# pihat.net
KiCad netlist of a schematic drawn in EAGLE
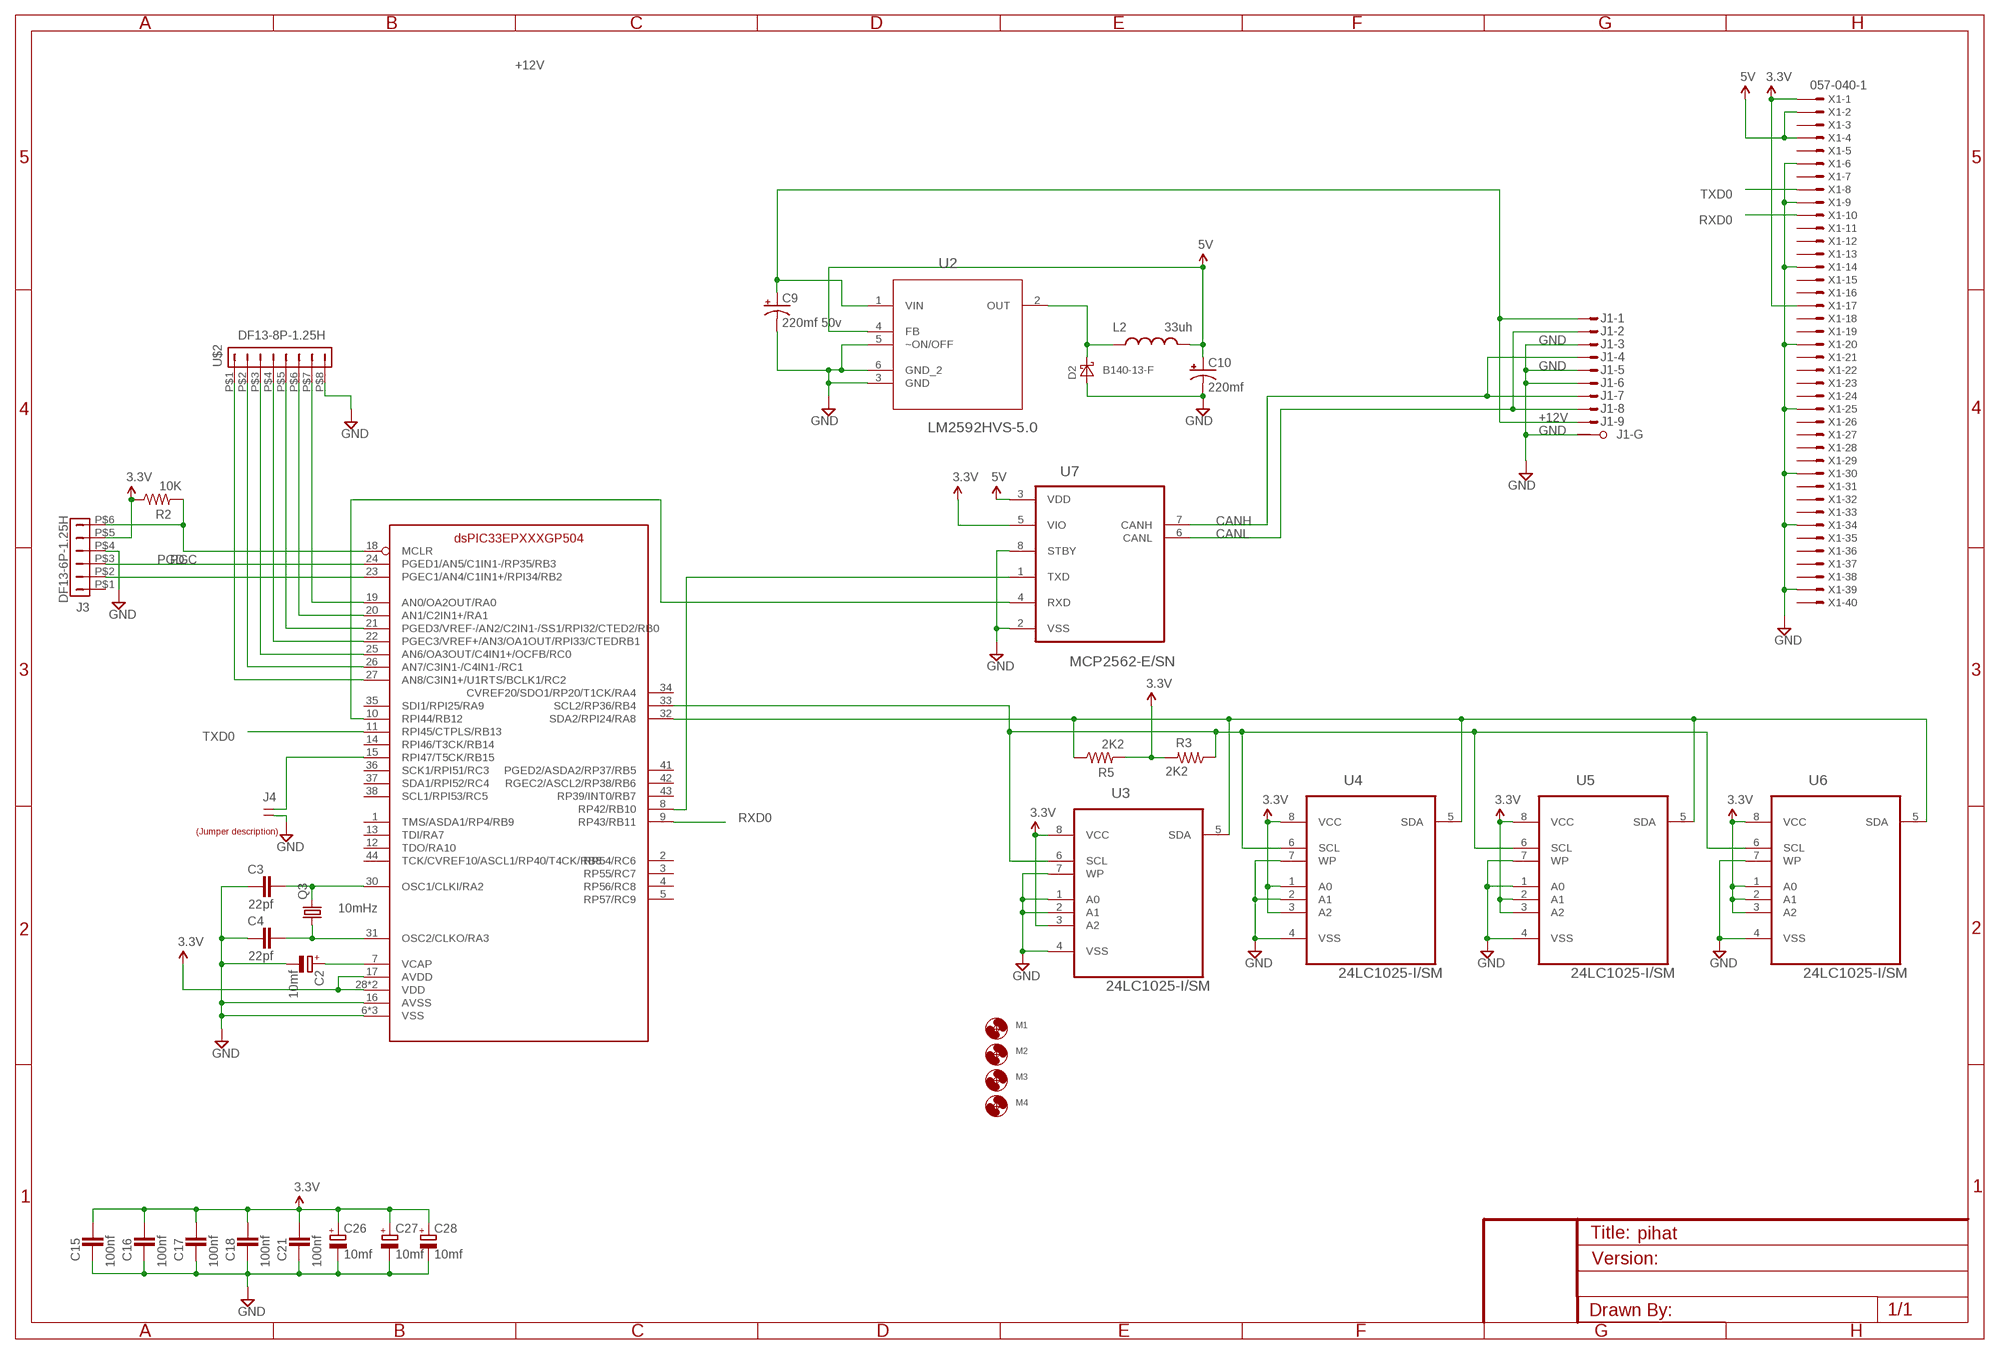
[diagram p0: schematic, sheet 1]

(export (version "E")
  (design (tool "Eeschema 10.0.6"))
  (components
    (comp (ref "C2")
      (value "10mf")
      (footprint "eagle-import:SMC_A")
      (fields (field (name "PARTNO") "T491A106K004AT"))
      (libsource (lib "eagle-import") (part "CAPACITOR_POL-SMC_A"))
    )
    (comp (ref "C3")
      (value "22pf")
      (footprint "eagle-import:C805")
      (fields (field (name "PARTNO") "C0805C220J5GACTU"))
      (libsource (lib "eagle-import") (part "CAPACITOR_NPOL-0805"))
    )
    (comp (ref "C4")
      (value "22pf")
      (footprint "eagle-import:C805")
      (fields (field (name "PARTNO") "C0805C220J5GACTU"))
      (libsource (lib "eagle-import") (part "CAPACITOR_NPOL-0805"))
    )
    (comp (ref "C9")
      (value "220mf 50v")
      (footprint "eagle-import:EIA7343")
      (fields (field (name "PARTNO") "T545X227M016ATE035"))
      (libsource (lib "eagle-import") (part "CAP_POL7343"))
    )
    (comp (ref "C10")
      (value "220mf")
      (footprint "eagle-import:EIA7343")
      (fields (field (name "PARTNO") "T545X227M016ATE035"))
      (libsource (lib "eagle-import") (part "CAP_POL7343"))
    )
    (comp (ref "C15")
      (value "100nf")
      (footprint "eagle-import:C805")
      (fields (field (name "PARTNO") "CL21F104ZBCNNNC"))
      (libsource (lib "eagle-import") (part "CAPACITOR_NPOL-0805"))
    )
    (comp (ref "C16")
      (value "100nf")
      (footprint "eagle-import:C805")
      (fields (field (name "PARTNO") "CL21F104ZBCNNNC"))
      (libsource (lib "eagle-import") (part "CAPACITOR_NPOL-0805"))
    )
    (comp (ref "C17")
      (value "100nf")
      (footprint "eagle-import:C805")
      (fields (field (name "PARTNO") "CL21F104ZBCNNNC"))
      (libsource (lib "eagle-import") (part "CAPACITOR_NPOL-0805"))
    )
    (comp (ref "C18")
      (value "100nf")
      (footprint "eagle-import:C805")
      (fields (field (name "PARTNO") "CL21F104ZBCNNNC"))
      (libsource (lib "eagle-import") (part "CAPACITOR_NPOL-0805"))
    )
    (comp (ref "C21")
      (value "100nf")
      (footprint "eagle-import:C805")
      (fields (field (name "PARTNO") "CL21F104ZBCNNNC"))
      (libsource (lib "eagle-import") (part "CAPACITOR_NPOL-0805"))
    )
    (comp (ref "C26")
      (value "10mf")
      (footprint "eagle-import:SMC_A")
      (fields (field (name "PARTNO") "T491A106K004AT"))
      (libsource (lib "eagle-import") (part "CAPACITOR_POL-SMC_A"))
    )
    (comp (ref "C27")
      (value "10mf")
      (footprint "eagle-import:SMC_A")
      (fields (field (name "PARTNO") "T491A106K004AT"))
      (libsource (lib "eagle-import") (part "CAPACITOR_POL-SMC_A"))
    )
    (comp (ref "C28")
      (value "10mf")
      (footprint "eagle-import:SMC_A")
      (fields (field (name "PARTNO") "T491A106K004AT"))
      (libsource (lib "eagle-import") (part "CAPACITOR_POL-SMC_A"))
    )
    (comp (ref "D2")
      (value "B140-13-F")
      (footprint "eagle-import:SMA")
      (libsource (lib "eagle-import") (part "DIODE-SCHOTTKY-SMA"))
    )
    (comp (ref "J1")
      (value "M09VPS")
      (footprint "eagle-import:M09VP")
      (fields (field (name "PARTNO") "1-1634218-2"))
      (libsource (lib "eagle-import") (part "M09VPS"))
    )
    (comp (ref "J3")
      (value "DF13-6P-1.25H")
      (footprint "eagle-import:DF13A-6P-1.25H")
      (fields (field (name "PARTNO") "DF13A-6P-1.25H(20)"))
      (libsource (lib "eagle-import") (part "DF13-6P-1.25H"))
    )
    (comp (ref "J4")
      (value "JUMPER-1X2")
      (footprint "eagle-import:JUMPER-1X2")
      (fields (field (name "PARTNO") "M20-9770246"))
      (libsource (lib "eagle-import") (part "JUMPER-1X2"))
    )
    (comp (ref "L2")
      (value "33uh")
      (footprint "eagle-import:1812")
      (fields (field (name "PARTNO") "B78108S1333K"))
      (libsource (lib "eagle-import") (part "INDUCTOR"))
    )
    (comp (ref "M1")
      (value "MOUNT-HOLE2.8")
      (footprint "eagle-import:2,8")
      (libsource (lib "eagle-import") (part "MOUNT-HOLE2.8"))
    )
    (comp (ref "M2")
      (value "MOUNT-HOLE2.8")
      (footprint "eagle-import:2,8")
      (libsource (lib "eagle-import") (part "MOUNT-HOLE2.8"))
    )
    (comp (ref "M3")
      (value "MOUNT-HOLE2.8")
      (footprint "eagle-import:2,8")
      (libsource (lib "eagle-import") (part "MOUNT-HOLE2.8"))
    )
    (comp (ref "M4")
      (value "MOUNT-HOLE2.8")
      (footprint "eagle-import:2,8")
      (libsource (lib "eagle-import") (part "MOUNT-HOLE2.8"))
    )
    (comp (ref "Q3")
      (value "10mHz")
      (footprint "eagle-import:HC49_S")
      (fields (field (name "PARTNO") "ATS100B-E"))
      (libsource (lib "eagle-import") (part "CRYSTALHC49S"))
    )
    (comp (ref "R2")
      (value "10K")
      (footprint "eagle-import:0603-RES")
      (fields (field (name "PARTNO") "RC0603FR-0710KL"))
      (libsource (lib "eagle-import") (part "RESISTOR0603-RES"))
    )
    (comp (ref "R3")
      (value "2K2")
      (footprint "eagle-import:0603-RES")
      (fields (field (name "PARTNO") "RC0603FR-072K2L"))
      (libsource (lib "eagle-import") (part "RESISTOR0603-RES"))
    )
    (comp (ref "R5")
      (value "2K2")
      (footprint "eagle-import:0603-RES")
      (fields (field (name "PARTNO") "RC0603FR-072K2L"))
      (libsource (lib "eagle-import") (part "RESISTOR0603-RES"))
    )
    (comp (ref "U$1")
      (value "LABEL_JUMPER_1X2")
      (footprint "eagle-import:JUMP2_DESC")
      (fields (field (name "OFF") "Normal") (field (name "ON") "Reset"))
      (libsource (lib "eagle-import") (part "LABEL_JUMPER_1X2"))
    )
    (comp (ref "U$2")
      (value "DF13-8P-1.25H")
      (footprint "eagle-import:DF13A-8P-1.25H")
      (fields (field (name "PARTNO") "DF13-8P-1.25H(50)"))
      (libsource (lib "eagle-import") (part "DF13-8P-1.25H"))
    )
    (comp (ref "U1")
      (value "DSPIC33EPXXXGP504")
      (footprint "eagle-import:TQFP44")
      (fields (field (name "PARTNO") "DSPIC33EP512GP504-I/PT"))
      (libsource (lib "eagle-import") (part "DSPIC33EPXXXGP504"))
    )
    (comp (ref "U2")
      (value "LM2592HVS-5.0")
      (footprint "eagle-import:TO170P1435X457-5N")
      (fields (field (name "PARTNO") "LM2592HVSX-5.0/NOPB"))
      (libsource (lib "eagle-import") (part "LM2592HVS-5.0"))
    )
    (comp (ref "U3")
      (value "24LC1025-I/SM")
      (footprint "eagle-import:SOIC8-N_MC")
      (fields (field (name "PARTNO") "24LC1025T-I/SN"))
      (libsource (lib "eagle-import") (part "24LC1025-I/SM"))
    )
    (comp (ref "U4")
      (value "24LC1025-I/SM")
      (footprint "eagle-import:SOIC8-N_MC")
      (fields (field (name "PARTNO") "24LC1025T-I/SN"))
      (libsource (lib "eagle-import") (part "24LC1025-I/SM"))
    )
    (comp (ref "U5")
      (value "24LC1025-I/SM")
      (footprint "eagle-import:SOIC8-N_MC")
      (fields (field (name "PARTNO") "24LC1025T-I/SN"))
      (libsource (lib "eagle-import") (part "24LC1025-I/SM"))
    )
    (comp (ref "U6")
      (value "24LC1025-I/SM")
      (footprint "eagle-import:SOIC8-N_MC")
      (fields (field (name "PARTNO") "24LC1025T-I/SN"))
      (libsource (lib "eagle-import") (part "24LC1025-I/SM"))
    )
    (comp (ref "U7")
      (value "MCP2562-E/SN")
      (footprint "eagle-import:SOIC-8N")
      (libsource (lib "eagle-import") (part "MCP2562-E/SN"))
    )
    (comp (ref "X1")
      (value "057-040-1")
      (footprint "eagle-import:057-040-1")
      (libsource (lib "eagle-import") (part "057-040-1"))
    )
  )
  (nets
    (net (code "1") (name "/+12V") (class "Default")
      (node (ref "C9") (pin "A") (pinfunction "+_A") (pintype "passive"))
      (node (ref "J1") (pin "1") (pinfunction "M_1") (pintype "passive"))
      (node (ref "J1") (pin "9") (pinfunction "M_9") (pintype "passive"))
      (node (ref "U2") (pin "1") (pinfunction "VIN_1") (pintype "power_in"))
    )
    (net (code "2") (name "/CANH") (class "Default")
      (node (ref "J1") (pin "4") (pinfunction "M_4") (pintype "passive"))
      (node (ref "J1") (pin "7") (pinfunction "M_7") (pintype "passive"))
      (node (ref "U7") (pin "7") (pinfunction "CANH_7") (pintype "bidirectional"))
    )
    (net (code "3") (name "/CANL") (class "Default")
      (node (ref "J1") (pin "2") (pinfunction "M_2") (pintype "passive"))
      (node (ref "J1") (pin "8") (pinfunction "M_8") (pintype "passive"))
      (node (ref "U7") (pin "6") (pinfunction "CANL_6") (pintype "bidirectional"))
    )
    (net (code "4") (name "/PGC") (class "Default")
      (node (ref "J3") (pin "P$2") (pinfunction "2_P$2") (pintype "passive"))
      (node (ref "U1") (pin "23") (pinfunction "PGEC1/AN4/C1IN1+/RPI34/RB2_23") (pintype "bidirectional"))
    )
    (net (code "5") (name "/PGD") (class "Default")
      (node (ref "J3") (pin "P$3") (pinfunction "3_P$3") (pintype "passive"))
      (node (ref "U1") (pin "24") (pinfunction "PGED1/AN5/C1IN1-/RP35/RB3_24") (pintype "bidirectional"))
    )
    (net (code "6") (name "/RXD0") (class "Default")
      (node (ref "U1") (pin "9") (pinfunction "RP43/RB11_9") (pintype "bidirectional"))
      (node (ref "X1") (pin "10") (pinfunction "S_10") (pintype "passive"))
    )
    (net (code "7") (name "/TXD0") (class "Default")
      (node (ref "U1") (pin "11") (pinfunction "RPI45/CTPLS/RB13_11") (pintype "bidirectional"))
      (node (ref "X1") (pin "8") (pinfunction "S_8") (pintype "passive"))
    )
    (net (code "8") (name "3.3V") (class "Default")
      (node (ref "C15") (pin "1") (pinfunction "1_1") (pintype "passive"))
      (node (ref "C16") (pin "1") (pinfunction "1_1") (pintype "passive"))
      (node (ref "C17") (pin "1") (pinfunction "1_1") (pintype "passive"))
      (node (ref "C18") (pin "1") (pinfunction "1_1") (pintype "passive"))
      (node (ref "C21") (pin "1") (pinfunction "1_1") (pintype "passive"))
      (node (ref "C26") (pin "+") (pinfunction "+_+") (pintype "passive"))
      (node (ref "C27") (pin "+") (pinfunction "+_+") (pintype "passive"))
      (node (ref "C28") (pin "+") (pinfunction "+_+") (pintype "passive"))
      (node (ref "J3") (pin "P$5") (pinfunction "5_P$5") (pintype "passive"))
      (node (ref "R2") (pin "1") (pinfunction "1_1") (pintype "passive"))
      (node (ref "R3") (pin "2") (pinfunction "2_2") (pintype "passive"))
      (node (ref "R5") (pin "2") (pinfunction "2_2") (pintype "passive"))
      (node (ref "U1") (pin "17") (pinfunction "AVDD_17") (pintype "bidirectional"))
      (node (ref "U1") (pin "28") (pinfunction "VDD_28") (pintype "bidirectional"))
      (node (ref "U1") (pin "40") (pinfunction "VDD_40") (pintype "bidirectional"))
      (node (ref "U3") (pin "3") (pinfunction "A2_3") (pintype "input"))
      (node (ref "U3") (pin "8") (pinfunction "VCC_8") (pintype "power_in"))
      (node (ref "U4") (pin "1") (pinfunction "A0_1") (pintype "input"))
      (node (ref "U4") (pin "3") (pinfunction "A2_3") (pintype "input"))
      (node (ref "U4") (pin "8") (pinfunction "VCC_8") (pintype "power_in"))
      (node (ref "U5") (pin "2") (pinfunction "A1_2") (pintype "input"))
      (node (ref "U5") (pin "3") (pinfunction "A2_3") (pintype "input"))
      (node (ref "U5") (pin "8") (pinfunction "VCC_8") (pintype "power_in"))
      (node (ref "U6") (pin "1") (pinfunction "A0_1") (pintype "input"))
      (node (ref "U6") (pin "2") (pinfunction "A1_2") (pintype "input"))
      (node (ref "U6") (pin "3") (pinfunction "A2_3") (pintype "input"))
      (node (ref "U6") (pin "8") (pinfunction "VCC_8") (pintype "power_in"))
      (node (ref "U7") (pin "5") (pinfunction "VIO_5") (pintype "power_in"))
      (node (ref "X1") (pin "1") (pinfunction "S_1") (pintype "passive"))
      (node (ref "X1") (pin "17") (pinfunction "S_17") (pintype "passive"))
    )
    (net (code "9") (name "5V") (class "Default")
      (node (ref "C10") (pin "A") (pinfunction "+_A") (pintype "passive"))
      (node (ref "L2") (pin "2") (pinfunction "2_2") (pintype "passive"))
      (node (ref "U2") (pin "4") (pinfunction "FB_4") (pintype "input"))
      (node (ref "U7") (pin "3") (pinfunction "VDD_3") (pintype "power_in"))
      (node (ref "X1") (pin "2") (pinfunction "S_2") (pintype "passive"))
      (node (ref "X1") (pin "4") (pinfunction "S_4") (pintype "passive"))
    )
    (net (code "10") (name "GND") (class "Default")
      (node (ref "C10") (pin "C") (pinfunction "-_C") (pintype "passive"))
      (node (ref "C15") (pin "2") (pinfunction "2_2") (pintype "passive"))
      (node (ref "C16") (pin "2") (pinfunction "2_2") (pintype "passive"))
      (node (ref "C17") (pin "2") (pinfunction "2_2") (pintype "passive"))
      (node (ref "C18") (pin "2") (pinfunction "2_2") (pintype "passive"))
      (node (ref "C2") (pin "-") (pinfunction "-_-") (pintype "passive"))
      (node (ref "C21") (pin "2") (pinfunction "2_2") (pintype "passive"))
      (node (ref "C26") (pin "-") (pinfunction "-_-") (pintype "passive"))
      (node (ref "C27") (pin "-") (pinfunction "-_-") (pintype "passive"))
      (node (ref "C28") (pin "-") (pinfunction "-_-") (pintype "passive"))
      (node (ref "C3") (pin "2") (pinfunction "2_2") (pintype "passive"))
      (node (ref "C4") (pin "2") (pinfunction "2_2") (pintype "passive"))
      (node (ref "C9") (pin "C") (pinfunction "-_C") (pintype "passive"))
      (node (ref "D2") (pin "A") (pinfunction "A_A") (pintype "passive"))
      (node (ref "J1") (pin "3") (pinfunction "M_3") (pintype "passive"))
      (node (ref "J1") (pin "5") (pinfunction "M_5") (pintype "passive"))
      (node (ref "J1") (pin "6") (pinfunction "M_6") (pintype "passive"))
      (node (ref "J1") (pin "G1") (pinfunction "G1_G1") (pintype "passive"))
      (node (ref "J3") (pin "P$4") (pinfunction "4_P$4") (pintype "passive"))
      (node (ref "J4") (pin "2") (pinfunction "2_2") (pintype "bidirectional"))
      (node (ref "U$2") (pin "P$8") (pinfunction "8_P$8") (pintype "passive"))
      (node (ref "U1") (pin "16") (pinfunction "AVSS_16") (pintype "bidirectional"))
      (node (ref "U1") (pin "29") (pinfunction "VSS_29") (pintype "bidirectional"))
      (node (ref "U1") (pin "39") (pinfunction "VSS_39") (pintype "bidirectional"))
      (node (ref "U1") (pin "6") (pinfunction "VSS_6") (pintype "bidirectional"))
      (node (ref "U2") (pin "3") (pinfunction "GND_3") (pintype "passive"))
      (node (ref "U2") (pin "5") (pinfunction "~{ON/OFF}_5") (pintype "input"))
      (node (ref "U2") (pin "6") (pinfunction "GND_2_6") (pintype "passive"))
      (node (ref "U3") (pin "1") (pinfunction "A0_1") (pintype "input"))
      (node (ref "U3") (pin "2") (pinfunction "A1_2") (pintype "input"))
      (node (ref "U3") (pin "4") (pinfunction "VSS_4") (pintype "passive"))
      (node (ref "U3") (pin "7") (pinfunction "WP_7") (pintype "input"))
      (node (ref "U4") (pin "2") (pinfunction "A1_2") (pintype "input"))
      (node (ref "U4") (pin "4") (pinfunction "VSS_4") (pintype "passive"))
      (node (ref "U4") (pin "7") (pinfunction "WP_7") (pintype "input"))
      (node (ref "U5") (pin "1") (pinfunction "A0_1") (pintype "input"))
      (node (ref "U5") (pin "4") (pinfunction "VSS_4") (pintype "passive"))
      (node (ref "U5") (pin "7") (pinfunction "WP_7") (pintype "input"))
      (node (ref "U6") (pin "4") (pinfunction "VSS_4") (pintype "passive"))
      (node (ref "U6") (pin "7") (pinfunction "WP_7") (pintype "input"))
      (node (ref "U7") (pin "2") (pinfunction "VSS_2") (pintype "power_in"))
      (node (ref "U7") (pin "8") (pinfunction "STBY_8") (pintype "input"))
      (node (ref "X1") (pin "14") (pinfunction "S_14") (pintype "passive"))
      (node (ref "X1") (pin "20") (pinfunction "S_20") (pintype "passive"))
      (node (ref "X1") (pin "25") (pinfunction "S_25") (pintype "passive"))
      (node (ref "X1") (pin "30") (pinfunction "S_30") (pintype "passive"))
      (node (ref "X1") (pin "34") (pinfunction "S_34") (pintype "passive"))
      (node (ref "X1") (pin "39") (pinfunction "S_39") (pintype "passive"))
      (node (ref "X1") (pin "6") (pinfunction "S_6") (pintype "passive"))
      (node (ref "X1") (pin "9") (pinfunction "S_9") (pintype "passive"))
    )
    (net (code "11") (name "Net-(J3-6)") (class "Default")
      (node (ref "J3") (pin "P$6") (pinfunction "6_P$6") (pintype "passive"))
      (node (ref "R2") (pin "2") (pinfunction "2_2") (pintype "passive"))
      (node (ref "U1") (pin "18") (pinfunction "MCLR_18") (pintype "input"))
    )
    (net (code "12") (name "Net-(U$2-1)") (class "Default")
      (node (ref "U$2") (pin "P$1") (pinfunction "1_P$1") (pintype "passive"))
      (node (ref "U1") (pin "27") (pinfunction "AN8/C3IN1+/U1RTS/BCLK1/RC2_27") (pintype "bidirectional"))
    )
    (net (code "13") (name "Net-(U$2-2)") (class "Default")
      (node (ref "U$2") (pin "P$2") (pinfunction "2_P$2") (pintype "passive"))
      (node (ref "U1") (pin "26") (pinfunction "AN7/C3IN1-/C4IN1-/RC1_26") (pintype "bidirectional"))
    )
    (net (code "14") (name "Net-(U$2-3)") (class "Default")
      (node (ref "U$2") (pin "P$3") (pinfunction "3_P$3") (pintype "passive"))
      (node (ref "U1") (pin "25") (pinfunction "AN6/OA3OUT/C4IN1+/OCFB/RC0_25") (pintype "bidirectional"))
    )
    (net (code "15") (name "Net-(U$2-4)") (class "Default")
      (node (ref "U$2") (pin "P$4") (pinfunction "4_P$4") (pintype "passive"))
      (node (ref "U1") (pin "22") (pinfunction "PGEC3/VREF+/AN3/OA1OUT/RPI33/CTEDRB1_22") (pintype "bidirectional"))
    )
    (net (code "16") (name "Net-(U$2-5)") (class "Default")
      (node (ref "U$2") (pin "P$5") (pinfunction "5_P$5") (pintype "passive"))
      (node (ref "U1") (pin "21") (pinfunction "PGED3/VREF-/AN2/C2IN1-/SS1/RPI32/CTED2/RB0_21") (pintype "bidirectional"))
    )
    (net (code "17") (name "Net-(U$2-6)") (class "Default")
      (node (ref "U$2") (pin "P$6") (pinfunction "6_P$6") (pintype "passive"))
      (node (ref "U1") (pin "20") (pinfunction "AN1/C2IN1+/RA1_20") (pintype "bidirectional"))
    )
    (net (code "18") (name "Net-(U$2-7)") (class "Default")
      (node (ref "U$2") (pin "P$7") (pinfunction "7_P$7") (pintype "passive"))
      (node (ref "U1") (pin "19") (pinfunction "AN0/OA2OUT/RA0_19") (pintype "bidirectional"))
    )
    (net (code "19") (name "Net-(U1-OSC1{slash}CLKI{slash}RA2)") (class "Default")
      (node (ref "C3") (pin "1") (pinfunction "1_1") (pintype "passive"))
      (node (ref "Q3") (pin "2") (pinfunction "2_2") (pintype "passive"))
      (node (ref "U1") (pin "30") (pinfunction "OSC1/CLKI/RA2_30") (pintype "bidirectional"))
    )
    (net (code "20") (name "Net-(U1-OSC2{slash}CLKO{slash}RA3)") (class "Default")
      (node (ref "C4") (pin "1") (pinfunction "1_1") (pintype "passive"))
      (node (ref "Q3") (pin "1") (pinfunction "1_1") (pintype "passive"))
      (node (ref "U1") (pin "31") (pinfunction "OSC2/CLKO/RA3_31") (pintype "bidirectional"))
    )
    (net (code "21") (name "Net-(U1-RP42{slash}RB10)") (class "Default")
      (node (ref "U1") (pin "8") (pinfunction "RP42/RB10_8") (pintype "bidirectional"))
      (node (ref "U7") (pin "1") (pinfunction "TXD_1") (pintype "input"))
    )
    (net (code "22") (name "Net-(U1-RPI44{slash}RB12)") (class "Default")
      (node (ref "U1") (pin "10") (pinfunction "RPI44/RB12_10") (pintype "bidirectional"))
      (node (ref "U7") (pin "4") (pinfunction "RXD_4") (pintype "output"))
    )
    (net (code "23") (name "Net-(U1-RPI47{slash}T5CK{slash}RB15)") (class "Default")
      (node (ref "J4") (pin "1") (pinfunction "1_1") (pintype "bidirectional"))
      (node (ref "U1") (pin "15") (pinfunction "RPI47/T5CK/RB15_15") (pintype "bidirectional"))
    )
    (net (code "24") (name "Net-(U1-SCL2{slash}RP36{slash}RB4)") (class "Default")
      (node (ref "R3") (pin "1") (pinfunction "1_1") (pintype "passive"))
      (node (ref "U1") (pin "33") (pinfunction "SCL2/RP36/RB4_33") (pintype "bidirectional"))
      (node (ref "U3") (pin "6") (pinfunction "SCL_6") (pintype "input"))
      (node (ref "U4") (pin "6") (pinfunction "SCL_6") (pintype "input"))
      (node (ref "U5") (pin "6") (pinfunction "SCL_6") (pintype "input"))
      (node (ref "U6") (pin "6") (pinfunction "SCL_6") (pintype "input"))
    )
    (net (code "25") (name "Net-(U1-SDA2{slash}RPI24{slash}RA8)") (class "Default")
      (node (ref "R5") (pin "1") (pinfunction "1_1") (pintype "passive"))
      (node (ref "U1") (pin "32") (pinfunction "SDA2/RPI24/RA8_32") (pintype "bidirectional"))
      (node (ref "U3") (pin "5") (pinfunction "SDA_5") (pintype "bidirectional"))
      (node (ref "U4") (pin "5") (pinfunction "SDA_5") (pintype "bidirectional"))
      (node (ref "U5") (pin "5") (pinfunction "SDA_5") (pintype "bidirectional"))
      (node (ref "U6") (pin "5") (pinfunction "SDA_5") (pintype "bidirectional"))
    )
    (net (code "26") (name "Net-(U1-VCAP)") (class "Default")
      (node (ref "C2") (pin "+") (pinfunction "+_+") (pintype "passive"))
      (node (ref "U1") (pin "7") (pinfunction "VCAP_7") (pintype "bidirectional"))
    )
    (net (code "27") (name "Net-(U2-OUT)") (class "Default")
      (node (ref "D2") (pin "C") (pinfunction "C_C") (pintype "passive"))
      (node (ref "L2") (pin "1") (pinfunction "1_1") (pintype "passive"))
      (node (ref "U2") (pin "2") (pinfunction "OUT_2") (pintype "output"))
    )
    (net (code "28") (name "unconnected-(J1-PadG2)") (class "Default")
      (node (ref "J1") (pin "G2") (pinfunction "G2_G2") (pintype "passive"))
    )
    (net (code "29") (name "unconnected-(J3-1-PadP$1)") (class "Default")
      (node (ref "J3") (pin "P$1") (pinfunction "1_P$1") (pintype "passive"))
    )
    (net (code "30") (name "unconnected-(U1-CVREF20{slash}SDO1{slash}RP20{slash}T1CK{slash}RA4-Pad34)") (class "Default")
      (node (ref "U1") (pin "34") (pinfunction "CVREF20/SDO1/RP20/T1CK/RA4_34") (pintype "bidirectional"))
    )
    (net (code "31") (name "unconnected-(U1-PGED2{slash}ASDA2{slash}RP37{slash}RB5-Pad41)") (class "Default")
      (node (ref "U1") (pin "41") (pinfunction "PGED2/ASDA2/RP37/RB5_41") (pintype "bidirectional"))
    )
    (net (code "32") (name "unconnected-(U1-RGEC2{slash}ASCL2{slash}RP38{slash}RB6-Pad42)") (class "Default")
      (node (ref "U1") (pin "42") (pinfunction "RGEC2/ASCL2/RP38/RB6_42") (pintype "bidirectional"))
    )
    (net (code "33") (name "unconnected-(U1-RP39{slash}INT0{slash}RB7-Pad43)") (class "Default")
      (node (ref "U1") (pin "43") (pinfunction "RP39/INT0/RB7_43") (pintype "bidirectional"))
    )
    (net (code "34") (name "unconnected-(U1-RP54{slash}RC6-Pad2)") (class "Default")
      (node (ref "U1") (pin "2") (pinfunction "RP54/RC6_2") (pintype "bidirectional"))
    )
    (net (code "35") (name "unconnected-(U1-RP55{slash}RC7-Pad3)") (class "Default")
      (node (ref "U1") (pin "3") (pinfunction "RP55/RC7_3") (pintype "bidirectional"))
    )
    (net (code "36") (name "unconnected-(U1-RP56{slash}RC8-Pad4)") (class "Default")
      (node (ref "U1") (pin "4") (pinfunction "RP56/RC8_4") (pintype "bidirectional"))
    )
    (net (code "37") (name "unconnected-(U1-RP57{slash}RC9-Pad5)") (class "Default")
      (node (ref "U1") (pin "5") (pinfunction "RP57/RC9_5") (pintype "bidirectional"))
    )
    (net (code "38") (name "unconnected-(U1-RPI46{slash}T3CK{slash}RB14-Pad14)") (class "Default")
      (node (ref "U1") (pin "14") (pinfunction "RPI46/T3CK/RB14_14") (pintype "bidirectional"))
    )
    (net (code "39") (name "unconnected-(U1-SCK1{slash}RPI51{slash}RC3-Pad36)") (class "Default")
      (node (ref "U1") (pin "36") (pinfunction "SCK1/RPI51/RC3_36") (pintype "bidirectional"))
    )
    (net (code "40") (name "unconnected-(U1-SCL1{slash}RPI53{slash}RC5-Pad38)") (class "Default")
      (node (ref "U1") (pin "38") (pinfunction "SCL1/RPI53/RC5_38") (pintype "bidirectional"))
    )
    (net (code "41") (name "unconnected-(U1-SDA1{slash}RPI52{slash}RC4-Pad37)") (class "Default")
      (node (ref "U1") (pin "37") (pinfunction "SDA1/RPI52/RC4_37") (pintype "bidirectional"))
    )
    (net (code "42") (name "unconnected-(U1-SDI1{slash}RPI25{slash}RA9-Pad35)") (class "Default")
      (node (ref "U1") (pin "35") (pinfunction "SDI1/RPI25/RA9_35") (pintype "bidirectional"))
    )
    (net (code "43") (name "unconnected-(U1-TCK{slash}CVREF10{slash}ASCL1{slash}RP40{slash}T4CK{slash}RB8-Pad44)") (class "Default")
      (node (ref "U1") (pin "44") (pinfunction "TCK/CVREF10/ASCL1/RP40/T4CK/RB8_44") (pintype "bidirectional"))
    )
    (net (code "44") (name "unconnected-(U1-TDI{slash}RA7-Pad13)") (class "Default")
      (node (ref "U1") (pin "13") (pinfunction "TDI/RA7_13") (pintype "bidirectional"))
    )
    (net (code "45") (name "unconnected-(U1-TDO{slash}RA10-Pad12)") (class "Default")
      (node (ref "U1") (pin "12") (pinfunction "TDO/RA10_12") (pintype "bidirectional"))
    )
    (net (code "46") (name "unconnected-(U1-TMS{slash}ASDA1{slash}RP4{slash}RB9-Pad1)") (class "Default")
      (node (ref "U1") (pin "1") (pinfunction "TMS/ASDA1/RP4/RB9_1") (pintype "bidirectional"))
    )
    (net (code "47") (name "unconnected-(X1AA-S-Pad33)") (class "Default")
      (node (ref "X1") (pin "33") (pinfunction "S_33") (pintype "passive"))
    )
    (net (code "48") (name "unconnected-(X1AC-S-Pad35)") (class "Default")
      (node (ref "X1") (pin "35") (pinfunction "S_35") (pintype "passive"))
    )
    (net (code "49") (name "unconnected-(X1AD-S-Pad36)") (class "Default")
      (node (ref "X1") (pin "36") (pinfunction "S_36") (pintype "passive"))
    )
    (net (code "50") (name "unconnected-(X1AE-S-Pad37)") (class "Default")
      (node (ref "X1") (pin "37") (pinfunction "S_37") (pintype "passive"))
    )
    (net (code "51") (name "unconnected-(X1AF-S-Pad38)") (class "Default")
      (node (ref "X1") (pin "38") (pinfunction "S_38") (pintype "passive"))
    )
    (net (code "52") (name "unconnected-(X1AI-S-Pad40)") (class "Default")
      (node (ref "X1") (pin "40") (pinfunction "S_40") (pintype "passive"))
    )
    (net (code "53") (name "unconnected-(X1AJ-S-Pad5)") (class "Default")
      (node (ref "X1") (pin "5") (pinfunction "S_5") (pintype "passive"))
    )
    (net (code "54") (name "unconnected-(X1AL-S-Pad7)") (class "Default")
      (node (ref "X1") (pin "7") (pinfunction "S_7") (pintype "passive"))
    )
    (net (code "55") (name "unconnected-(X1C-S-Pad11)") (class "Default")
      (node (ref "X1") (pin "11") (pinfunction "S_11") (pintype "passive"))
    )
    (net (code "56") (name "unconnected-(X1D-S-Pad12)") (class "Default")
      (node (ref "X1") (pin "12") (pinfunction "S_12") (pintype "passive"))
    )
    (net (code "57") (name "unconnected-(X1E-S-Pad13)") (class "Default")
      (node (ref "X1") (pin "13") (pinfunction "S_13") (pintype "passive"))
    )
    (net (code "58") (name "unconnected-(X1G-S-Pad15)") (class "Default")
      (node (ref "X1") (pin "15") (pinfunction "S_15") (pintype "passive"))
    )
    (net (code "59") (name "unconnected-(X1H-S-Pad16)") (class "Default")
      (node (ref "X1") (pin "16") (pinfunction "S_16") (pintype "passive"))
    )
    (net (code "60") (name "unconnected-(X1J-S-Pad18)") (class "Default")
      (node (ref "X1") (pin "18") (pinfunction "S_18") (pintype "passive"))
    )
    (net (code "61") (name "unconnected-(X1K-S-Pad19)") (class "Default")
      (node (ref "X1") (pin "19") (pinfunction "S_19") (pintype "passive"))
    )
    (net (code "62") (name "unconnected-(X1N-S-Pad21)") (class "Default")
      (node (ref "X1") (pin "21") (pinfunction "S_21") (pintype "passive"))
    )
    (net (code "63") (name "unconnected-(X1O-S-Pad22)") (class "Default")
      (node (ref "X1") (pin "22") (pinfunction "S_22") (pintype "passive"))
    )
    (net (code "64") (name "unconnected-(X1P-S-Pad23)") (class "Default")
      (node (ref "X1") (pin "23") (pinfunction "S_23") (pintype "passive"))
    )
    (net (code "65") (name "unconnected-(X1Q-S-Pad24)") (class "Default")
      (node (ref "X1") (pin "24") (pinfunction "S_24") (pintype "passive"))
    )
    (net (code "66") (name "unconnected-(X1S-S-Pad26)") (class "Default")
      (node (ref "X1") (pin "26") (pinfunction "S_26") (pintype "passive"))
    )
    (net (code "67") (name "unconnected-(X1T-S-Pad27)") (class "Default")
      (node (ref "X1") (pin "27") (pinfunction "S_27") (pintype "passive"))
    )
    (net (code "68") (name "unconnected-(X1U-S-Pad28)") (class "Default")
      (node (ref "X1") (pin "28") (pinfunction "S_28") (pintype "passive"))
    )
    (net (code "69") (name "unconnected-(X1V-S-Pad29)") (class "Default")
      (node (ref "X1") (pin "29") (pinfunction "S_29") (pintype "passive"))
    )
    (net (code "70") (name "unconnected-(X1W-S-Pad3)") (class "Default")
      (node (ref "X1") (pin "3") (pinfunction "S_3") (pintype "passive"))
    )
    (net (code "71") (name "unconnected-(X1Y-S-Pad31)") (class "Default")
      (node (ref "X1") (pin "31") (pinfunction "S_31") (pintype "passive"))
    )
    (net (code "72") (name "unconnected-(X1Z-S-Pad32)") (class "Default")
      (node (ref "X1") (pin "32") (pinfunction "S_32") (pintype "passive"))
    )
  )
)
